# DRAM_TEMP_AD.net
KiCad netlist of a schematic drawn in Altium Designer
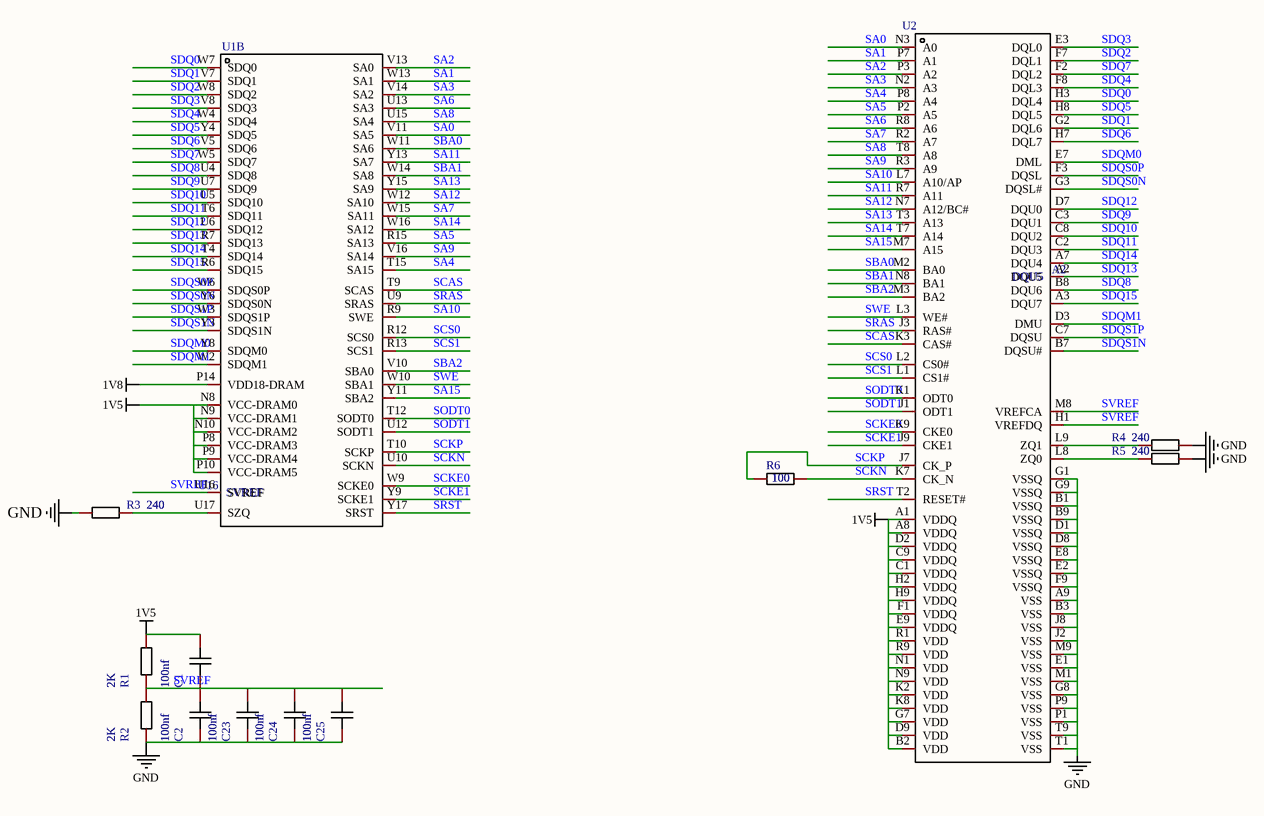
[diagram p0: DRAM_TEMP_AD.schdoc]

(export (version "E")
  (design (tool "Eeschema 10.0.6"))
  (components
    (comp (ref "C1")
      (value "100nf")
      (fields (field (name "NAME") "100nf"))
      (libsource (lib "altium-import") (part "root_1_C0402_1_"))
    )
    (comp (ref "C2")
      (value "100nf")
      (fields (field (name "NAME") "100nf"))
      (libsource (lib "altium-import") (part "root_1_C0402_2_"))
    )
    (comp (ref "C23")
      (value "100nf")
      (fields (field (name "NAME") "100nf"))
      (libsource (lib "altium-import") (part "root_1_C0402_2_"))
    )
    (comp (ref "C24")
      (value "100nf")
      (fields (field (name "NAME") "100nf"))
      (libsource (lib "altium-import") (part "root_1_C0402_2_"))
    )
    (comp (ref "C25")
      (value "100nf")
      (fields (field (name "NAME") "100nf"))
      (libsource (lib "altium-import") (part "root_1_C0402_2_"))
    )
    (comp (ref "R1")
      (value "2K")
      (fields (field (name "NAME") "2K"))
      (libsource (lib "altium-import") (part "root_1_R0402_1_1_"))
    )
    (comp (ref "R2")
      (value "2K")
      (fields (field (name "NAME") "2K"))
      (libsource (lib "altium-import") (part "root_1_R0402_1_"))
    )
    (comp (ref "R3")
      (value "240")
      (fields (field (name "NAME") "240"))
      (libsource (lib "altium-import") (part "root_0_R0402_1_"))
    )
    (comp (ref "R4")
      (value "240")
      (fields (field (name "NAME") "240"))
      (libsource (lib "altium-import") (part "root_0_R0402_1_"))
    )
    (comp (ref "R5")
      (value "240")
      (fields (field (name "NAME") "240"))
      (libsource (lib "altium-import") (part "root_0_R0402_1_"))
    )
    (comp (ref "R6")
      (value "100")
      (fields (field (name "NAME") "100"))
      (libsource (lib "altium-import") (part "root_0_R0402_1_"))
    )
    (comp (ref "U1")
      (value "~")
      (fields (field (name "NAME") "SVREF") (field (name "NUMBER") "U16"))
      (libsource (lib "altium-import") (part "root_0_Allwinner D1-H_"))
    )
    (comp (ref "U2")
      (value "~")
      (fields
        (field (name "MANUFACTURER") "HYNIX(海力士)")
        (field (name "MANUFACTURER PART") "H5TQ4G63EFR-RDC")
        (field (name "NAME") "DQU5")
        (field (name "NUMBER") "A2")
      )
      (libsource (lib "altium-import") (part "root_0_H5TQ4G63EFR-RDC_1_"))
    )
  )
  (nets
    (net (code "1") (name "/SA0") (class "Default")
      (node (ref "U1") (pin "V11") (pinfunction "SA5_V11") (pintype "passive"))
      (node (ref "U2") (pin "N3") (pinfunction "A0_N3") (pintype "passive"))
    )
    (net (code "2") (name "/SA1") (class "Default")
      (node (ref "U1") (pin "W13") (pinfunction "SA1_W13") (pintype "passive"))
      (node (ref "U2") (pin "P7") (pinfunction "A1_P7") (pintype "passive"))
    )
    (net (code "3") (name "/SA2") (class "Default")
      (node (ref "U1") (pin "V13") (pinfunction "SA0_V13") (pintype "passive"))
      (node (ref "U2") (pin "P3") (pinfunction "A2_P3") (pintype "passive"))
    )
    (net (code "4") (name "/SA3") (class "Default")
      (node (ref "U1") (pin "V14") (pinfunction "SA2_V14") (pintype "passive"))
      (node (ref "U2") (pin "N2") (pinfunction "A3_N2") (pintype "passive"))
    )
    (net (code "5") (name "/SA4") (class "Default")
      (node (ref "U1") (pin "T15") (pinfunction "SA15_T15") (pintype "passive"))
      (node (ref "U2") (pin "P8") (pinfunction "A4_P8") (pintype "passive"))
    )
    (net (code "6") (name "/SA5") (class "Default")
      (node (ref "U1") (pin "R15") (pinfunction "SA13_R15") (pintype "passive"))
      (node (ref "U2") (pin "P2") (pinfunction "A5_P2") (pintype "passive"))
    )
    (net (code "7") (name "/SA6") (class "Default")
      (node (ref "U1") (pin "U13") (pinfunction "SA3_U13") (pintype "passive"))
      (node (ref "U2") (pin "R8") (pinfunction "A6_R8") (pintype "passive"))
    )
    (net (code "8") (name "/SA7") (class "Default")
      (node (ref "U1") (pin "W15") (pinfunction "SA11_W15") (pintype "passive"))
      (node (ref "U2") (pin "R2") (pinfunction "A7_R2") (pintype "passive"))
    )
    (net (code "9") (name "/SA8") (class "Default")
      (node (ref "U1") (pin "U15") (pinfunction "SA4_U15") (pintype "passive"))
      (node (ref "U2") (pin "T8") (pinfunction "A8_T8") (pintype "passive"))
    )
    (net (code "10") (name "/SA9") (class "Default")
      (node (ref "U1") (pin "V16") (pinfunction "SA14_V16") (pintype "passive"))
      (node (ref "U2") (pin "R3") (pinfunction "A9_R3") (pintype "passive"))
    )
    (net (code "11") (name "/SA10") (class "Default")
      (node (ref "U1") (pin "R9") (pinfunction "SWE_R9") (pintype "passive"))
      (node (ref "U2") (pin "L7") (pinfunction "A10/AP_L7") (pintype "passive"))
    )
    (net (code "12") (name "/SA11") (class "Default")
      (node (ref "U1") (pin "Y13") (pinfunction "SA7_Y13") (pintype "passive"))
      (node (ref "U2") (pin "R7") (pinfunction "A11_R7") (pintype "passive"))
    )
    (net (code "13") (name "/SA12") (class "Default")
      (node (ref "U1") (pin "W12") (pinfunction "SA10_W12") (pintype "passive"))
      (node (ref "U2") (pin "N7") (pinfunction "A12/BC#_N7") (pintype "passive"))
    )
    (net (code "14") (name "/SA13") (class "Default")
      (node (ref "U1") (pin "Y15") (pinfunction "SA9_Y15") (pintype "passive"))
      (node (ref "U2") (pin "T3") (pinfunction "A13_T3") (pintype "passive"))
    )
    (net (code "15") (name "/SA14") (class "Default")
      (node (ref "U1") (pin "W16") (pinfunction "SA12_W16") (pintype "passive"))
      (node (ref "U2") (pin "T7") (pinfunction "A14_T7") (pintype "passive"))
    )
    (net (code "16") (name "/SA15") (class "Default")
      (node (ref "U1") (pin "Y11") (pinfunction "SBA2_Y11") (pintype "passive"))
      (node (ref "U2") (pin "M7") (pinfunction "A15_M7") (pintype "passive"))
    )
    (net (code "17") (name "/SBA0") (class "Default")
      (node (ref "U1") (pin "W11") (pinfunction "SA6_W11") (pintype "passive"))
      (node (ref "U2") (pin "M2") (pinfunction "BA0_M2") (pintype "passive"))
    )
    (net (code "18") (name "/SBA1") (class "Default")
      (node (ref "U1") (pin "W14") (pinfunction "SA8_W14") (pintype "passive"))
      (node (ref "U2") (pin "N8") (pinfunction "BA1_N8") (pintype "passive"))
    )
    (net (code "19") (name "/SBA2") (class "Default")
      (node (ref "U1") (pin "V10") (pinfunction "SBA0_V10") (pintype "passive"))
      (node (ref "U2") (pin "M3") (pinfunction "BA2_M3") (pintype "passive"))
    )
    (net (code "20") (name "/SCAS") (class "Default")
      (node (ref "U1") (pin "T9") (pinfunction "SCAS_T9") (pintype "passive"))
      (node (ref "U2") (pin "K3") (pinfunction "CAS#_K3") (pintype "passive"))
    )
    (net (code "21") (name "/SCKE0") (class "Default")
      (node (ref "U1") (pin "W9") (pinfunction "SCKE0_W9") (pintype "passive"))
      (node (ref "U2") (pin "K9") (pinfunction "CKE0_K9") (pintype "passive"))
    )
    (net (code "22") (name "/SCKE1") (class "Default")
      (node (ref "U1") (pin "Y9") (pinfunction "SCKE1_Y9") (pintype "passive"))
      (node (ref "U2") (pin "J9") (pinfunction "CKE1_J9") (pintype "passive"))
    )
    (net (code "23") (name "/SCKN") (class "Default")
      (node (ref "R6") (pin "2") (pinfunction "2_2") (pintype "passive"))
      (node (ref "U1") (pin "U10") (pinfunction "SCKN_U10") (pintype "passive"))
      (node (ref "U2") (pin "K7") (pinfunction "CK_N_K7") (pintype "passive"))
    )
    (net (code "24") (name "/SCKP") (class "Default")
      (node (ref "R6") (pin "1") (pinfunction "1_1") (pintype "passive"))
      (node (ref "U1") (pin "T10") (pinfunction "SCKP_T10") (pintype "passive"))
      (node (ref "U2") (pin "J7") (pinfunction "CK_P_J7") (pintype "passive"))
    )
    (net (code "25") (name "/SCS0") (class "Default")
      (node (ref "U1") (pin "R12") (pinfunction "SCS0_R12") (pintype "passive"))
      (node (ref "U2") (pin "L2") (pinfunction "CS0#_L2") (pintype "passive"))
    )
    (net (code "26") (name "/SCS1") (class "Default")
      (node (ref "U1") (pin "R13") (pinfunction "SCS1_R13") (pintype "passive"))
      (node (ref "U2") (pin "L1") (pinfunction "CS1#_L1") (pintype "passive"))
    )
    (net (code "27") (name "/SDQ0") (class "Default")
      (node (ref "U1") (pin "W7") (pinfunction "SDQ0_W7") (pintype "passive"))
      (node (ref "U2") (pin "H3") (pinfunction "DQL4_H3") (pintype "passive"))
    )
    (net (code "28") (name "/SDQ1") (class "Default")
      (node (ref "U1") (pin "V7") (pinfunction "SDQ1_V7") (pintype "passive"))
      (node (ref "U2") (pin "G2") (pinfunction "DQL6_G2") (pintype "passive"))
    )
    (net (code "29") (name "/SDQ2") (class "Default")
      (node (ref "U1") (pin "W8") (pinfunction "SDQ2_W8") (pintype "passive"))
      (node (ref "U2") (pin "F7") (pinfunction "DQL1_F7") (pintype "passive"))
    )
    (net (code "30") (name "/SDQ3") (class "Default")
      (node (ref "U1") (pin "V8") (pinfunction "SDQ3_V8") (pintype "passive"))
      (node (ref "U2") (pin "E3") (pinfunction "DQL0_E3") (pintype "passive"))
    )
    (net (code "31") (name "/SDQ4") (class "Default")
      (node (ref "U1") (pin "W4") (pinfunction "SDQ4_W4") (pintype "passive"))
      (node (ref "U2") (pin "F8") (pinfunction "DQL3_F8") (pintype "passive"))
    )
    (net (code "32") (name "/SDQ5") (class "Default")
      (node (ref "U1") (pin "Y4") (pinfunction "SDQ5_Y4") (pintype "passive"))
      (node (ref "U2") (pin "H8") (pinfunction "DQL5_H8") (pintype "passive"))
    )
    (net (code "33") (name "/SDQ6") (class "Default")
      (node (ref "U1") (pin "V5") (pinfunction "SDQ6_V5") (pintype "passive"))
      (node (ref "U2") (pin "H7") (pinfunction "DQL7_H7") (pintype "passive"))
    )
    (net (code "34") (name "/SDQ7") (class "Default")
      (node (ref "U1") (pin "W5") (pinfunction "SDQ7_W5") (pintype "passive"))
      (node (ref "U2") (pin "F2") (pinfunction "DQL2_F2") (pintype "passive"))
    )
    (net (code "35") (name "/SDQ8") (class "Default")
      (node (ref "U1") (pin "U4") (pinfunction "SDQ8_U4") (pintype "passive"))
      (node (ref "U2") (pin "B8") (pinfunction "DQU6_B8") (pintype "passive"))
    )
    (net (code "36") (name "/SDQ9") (class "Default")
      (node (ref "U1") (pin "U7") (pinfunction "SDQ9_U7") (pintype "passive"))
      (node (ref "U2") (pin "C3") (pinfunction "DQU1_C3") (pintype "passive"))
    )
    (net (code "37") (name "/SDQ10") (class "Default")
      (node (ref "U1") (pin "U5") (pinfunction "SDQ10_U5") (pintype "passive"))
      (node (ref "U2") (pin "C8") (pinfunction "DQU2_C8") (pintype "passive"))
    )
    (net (code "38") (name "/SDQ11") (class "Default")
      (node (ref "U1") (pin "T6") (pinfunction "SDQ11_T6") (pintype "passive"))
      (node (ref "U2") (pin "C2") (pinfunction "DQU3_C2") (pintype "passive"))
    )
    (net (code "39") (name "/SDQ12") (class "Default")
      (node (ref "U1") (pin "U6") (pinfunction "SDQ12_U6") (pintype "passive"))
      (node (ref "U2") (pin "D7") (pinfunction "DQU0_D7") (pintype "passive"))
    )
    (net (code "40") (name "/SDQ13") (class "Default")
      (node (ref "U1") (pin "R7") (pinfunction "SDQ13_R7") (pintype "passive"))
      (node (ref "U2") (pin "A2") (pinfunction "DQU5_A2") (pintype "passive"))
    )
    (net (code "41") (name "/SDQ14") (class "Default")
      (node (ref "U1") (pin "T4") (pinfunction "SDQ14_T4") (pintype "passive"))
      (node (ref "U2") (pin "A7") (pinfunction "DQU4_A7") (pintype "passive"))
    )
    (net (code "42") (name "/SDQ15") (class "Default")
      (node (ref "U1") (pin "R6") (pinfunction "SDQ15_R6") (pintype "passive"))
      (node (ref "U2") (pin "A3") (pinfunction "DQU7_A3") (pintype "passive"))
    )
    (net (code "43") (name "/SDQM0") (class "Default")
      (node (ref "U1") (pin "Y8") (pinfunction "SDQM0_Y8") (pintype "passive"))
      (node (ref "U2") (pin "E7") (pinfunction "DML_E7") (pintype "passive"))
    )
    (net (code "44") (name "/SDQM1") (class "Default")
      (node (ref "U1") (pin "W2") (pinfunction "SDQM1_W2") (pintype "passive"))
      (node (ref "U2") (pin "D3") (pinfunction "DMU_D3") (pintype "passive"))
    )
    (net (code "45") (name "/SDQS0N") (class "Default")
      (node (ref "U1") (pin "Y6") (pinfunction "SDQS0N_Y6") (pintype "passive"))
      (node (ref "U2") (pin "G3") (pinfunction "DQSL#_G3") (pintype "passive"))
    )
    (net (code "46") (name "/SDQS0P") (class "Default")
      (node (ref "U1") (pin "W6") (pinfunction "SDQS0P_W6") (pintype "passive"))
      (node (ref "U2") (pin "F3") (pinfunction "DQSL_F3") (pintype "passive"))
    )
    (net (code "47") (name "/SDQS1N") (class "Default")
      (node (ref "U1") (pin "Y3") (pinfunction "SDQS1N_Y3") (pintype "passive"))
      (node (ref "U2") (pin "B7") (pinfunction "DQSU#_B7") (pintype "passive"))
    )
    (net (code "48") (name "/SDQS1P") (class "Default")
      (node (ref "U1") (pin "W3") (pinfunction "SDQS1P_W3") (pintype "passive"))
      (node (ref "U2") (pin "C7") (pinfunction "DQSU_C7") (pintype "passive"))
    )
    (net (code "49") (name "/SODT0") (class "Default")
      (node (ref "U1") (pin "T12") (pinfunction "SODT0_T12") (pintype "passive"))
      (node (ref "U2") (pin "K1") (pinfunction "ODT0_K1") (pintype "passive"))
    )
    (net (code "50") (name "/SODT1") (class "Default")
      (node (ref "U1") (pin "U12") (pinfunction "SODT1_U12") (pintype "passive"))
      (node (ref "U2") (pin "J1") (pinfunction "ODT1_J1") (pintype "passive"))
    )
    (net (code "51") (name "/SRAS") (class "Default")
      (node (ref "U1") (pin "U9") (pinfunction "SRAS_U9") (pintype "passive"))
      (node (ref "U2") (pin "J3") (pinfunction "RAS#_J3") (pintype "passive"))
    )
    (net (code "52") (name "/SRST") (class "Default")
      (node (ref "U1") (pin "Y17") (pinfunction "SRST_Y17") (pintype "passive"))
      (node (ref "U2") (pin "T2") (pinfunction "RESET#_T2") (pintype "passive"))
    )
    (net (code "53") (name "/SVREF") (class "Default")
      (node (ref "C1") (pin "1") (pinfunction "1_1") (pintype "passive"))
      (node (ref "C2") (pin "2") (pinfunction "2_2") (pintype "passive"))
      (node (ref "C23") (pin "2") (pinfunction "2_2") (pintype "passive"))
      (node (ref "C24") (pin "2") (pinfunction "2_2") (pintype "passive"))
      (node (ref "C25") (pin "2") (pinfunction "2_2") (pintype "passive"))
      (node (ref "R1") (pin "1") (pinfunction "1_1") (pintype "passive"))
      (node (ref "R2") (pin "2") (pinfunction "2_2") (pintype "passive"))
      (node (ref "U1") (pin "U16") (pinfunction "SVREF_U16") (pintype "passive"))
      (node (ref "U2") (pin "H1") (pinfunction "VREFDQ_H1") (pintype "passive"))
      (node (ref "U2") (pin "M8") (pinfunction "VREFCA_M8") (pintype "passive"))
    )
    (net (code "54") (name "/SWE") (class "Default")
      (node (ref "U1") (pin "W10") (pinfunction "SBA1_W10") (pintype "passive"))
      (node (ref "U2") (pin "L3") (pinfunction "WE#_L3") (pintype "passive"))
    )
    (net (code "55") (name "1V5") (class "Default")
      (node (ref "C1") (pin "2") (pinfunction "2_2") (pintype "passive"))
      (node (ref "R1") (pin "2") (pinfunction "2_2") (pintype "passive"))
      (node (ref "U1") (pin "N10") (pinfunction "VCC-DRAM2_N10") (pintype "passive"))
      (node (ref "U1") (pin "N8") (pinfunction "VCC-DRAM0_N8") (pintype "passive"))
      (node (ref "U1") (pin "N9") (pinfunction "VCC-DRAM1_N9") (pintype "passive"))
      (node (ref "U1") (pin "P10") (pinfunction "VCC-DRAM5_P10") (pintype "passive"))
      (node (ref "U1") (pin "P8") (pinfunction "VCC-DRAM3_P8") (pintype "passive"))
      (node (ref "U1") (pin "P9") (pinfunction "VCC-DRAM4_P9") (pintype "passive"))
      (node (ref "U2") (pin "A1") (pinfunction "VDDQ_A1") (pintype "passive"))
      (node (ref "U2") (pin "A8") (pinfunction "VDDQ_A8") (pintype "passive"))
      (node (ref "U2") (pin "B2") (pinfunction "VDD_B2") (pintype "passive"))
      (node (ref "U2") (pin "C1") (pinfunction "VDDQ_C1") (pintype "passive"))
      (node (ref "U2") (pin "C9") (pinfunction "VDDQ_C9") (pintype "passive"))
      (node (ref "U2") (pin "D2") (pinfunction "VDDQ_D2") (pintype "passive"))
      (node (ref "U2") (pin "D9") (pinfunction "VDD_D9") (pintype "passive"))
      (node (ref "U2") (pin "E9") (pinfunction "VDDQ_E9") (pintype "passive"))
      (node (ref "U2") (pin "F1") (pinfunction "VDDQ_F1") (pintype "passive"))
      (node (ref "U2") (pin "G7") (pinfunction "VDD_G7") (pintype "passive"))
      (node (ref "U2") (pin "H2") (pinfunction "VDDQ_H2") (pintype "passive"))
      (node (ref "U2") (pin "H9") (pinfunction "VDDQ_H9") (pintype "passive"))
      (node (ref "U2") (pin "K2") (pinfunction "VDD_K2") (pintype "passive"))
      (node (ref "U2") (pin "K8") (pinfunction "VDD_K8") (pintype "passive"))
      (node (ref "U2") (pin "N1") (pinfunction "VDD_N1") (pintype "passive"))
      (node (ref "U2") (pin "N9") (pinfunction "VDD_N9") (pintype "passive"))
      (node (ref "U2") (pin "R1") (pinfunction "VDD_R1") (pintype "passive"))
      (node (ref "U2") (pin "R9") (pinfunction "VDD_R9") (pintype "passive"))
    )
    (net (code "56") (name "1V8") (class "Default")
      (node (ref "U1") (pin "P14") (pinfunction "VDD18-DRAM_P14") (pintype "passive"))
    )
    (net (code "57") (name "GND") (class "Default")
      (node (ref "C2") (pin "1") (pinfunction "1_1") (pintype "passive"))
      (node (ref "C23") (pin "1") (pinfunction "1_1") (pintype "passive"))
      (node (ref "C24") (pin "1") (pinfunction "1_1") (pintype "passive"))
      (node (ref "C25") (pin "1") (pinfunction "1_1") (pintype "passive"))
      (node (ref "R2") (pin "1") (pinfunction "1_1") (pintype "passive"))
      (node (ref "R3") (pin "1") (pinfunction "1_1") (pintype "passive"))
      (node (ref "R4") (pin "2") (pinfunction "2_2") (pintype "passive"))
      (node (ref "R5") (pin "2") (pinfunction "2_2") (pintype "passive"))
      (node (ref "U2") (pin "A9") (pinfunction "VSS_A9") (pintype "passive"))
      (node (ref "U2") (pin "B1") (pinfunction "VSSQ_B1") (pintype "passive"))
      (node (ref "U2") (pin "B3") (pinfunction "VSS_B3") (pintype "passive"))
      (node (ref "U2") (pin "B9") (pinfunction "VSSQ_B9") (pintype "passive"))
      (node (ref "U2") (pin "D1") (pinfunction "VSSQ_D1") (pintype "passive"))
      (node (ref "U2") (pin "D8") (pinfunction "VSSQ_D8") (pintype "passive"))
      (node (ref "U2") (pin "E1") (pinfunction "VSS_E1") (pintype "passive"))
      (node (ref "U2") (pin "E2") (pinfunction "VSSQ_E2") (pintype "passive"))
      (node (ref "U2") (pin "E8") (pinfunction "VSSQ_E8") (pintype "passive"))
      (node (ref "U2") (pin "F9") (pinfunction "VSSQ_F9") (pintype "passive"))
      (node (ref "U2") (pin "G1") (pinfunction "VSSQ_G1") (pintype "passive"))
      (node (ref "U2") (pin "G8") (pinfunction "VSS_G8") (pintype "passive"))
      (node (ref "U2") (pin "G9") (pinfunction "VSSQ_G9") (pintype "passive"))
      (node (ref "U2") (pin "J2") (pinfunction "VSS_J2") (pintype "passive"))
      (node (ref "U2") (pin "J8") (pinfunction "VSS_J8") (pintype "passive"))
      (node (ref "U2") (pin "M1") (pinfunction "VSS_M1") (pintype "passive"))
      (node (ref "U2") (pin "M9") (pinfunction "VSS_M9") (pintype "passive"))
      (node (ref "U2") (pin "P1") (pinfunction "VSS_P1") (pintype "passive"))
      (node (ref "U2") (pin "P9") (pinfunction "VSS_P9") (pintype "passive"))
      (node (ref "U2") (pin "T1") (pinfunction "VSS_T1") (pintype "passive"))
      (node (ref "U2") (pin "T9") (pinfunction "VSS_T9") (pintype "passive"))
    )
    (net (code "58") (name "Net-(U1B-SZQ)") (class "Default")
      (node (ref "R3") (pin "2") (pinfunction "2_2") (pintype "passive"))
      (node (ref "U1") (pin "U17") (pinfunction "SZQ_U17") (pintype "passive"))
    )
    (net (code "59") (name "Net-(U2-ZQ0)") (class "Default")
      (node (ref "R5") (pin "1") (pinfunction "1_1") (pintype "passive"))
      (node (ref "U2") (pin "L8") (pinfunction "ZQ0_L8") (pintype "passive"))
    )
    (net (code "60") (name "Net-(U2-ZQ1)") (class "Default")
      (node (ref "R4") (pin "1") (pinfunction "1_1") (pintype "passive"))
      (node (ref "U2") (pin "L9") (pinfunction "ZQ1_L9") (pintype "passive"))
    )
  )
)
